# pcb_benelli.net
KiCad netlist of a schematic drawn in Altium Designer
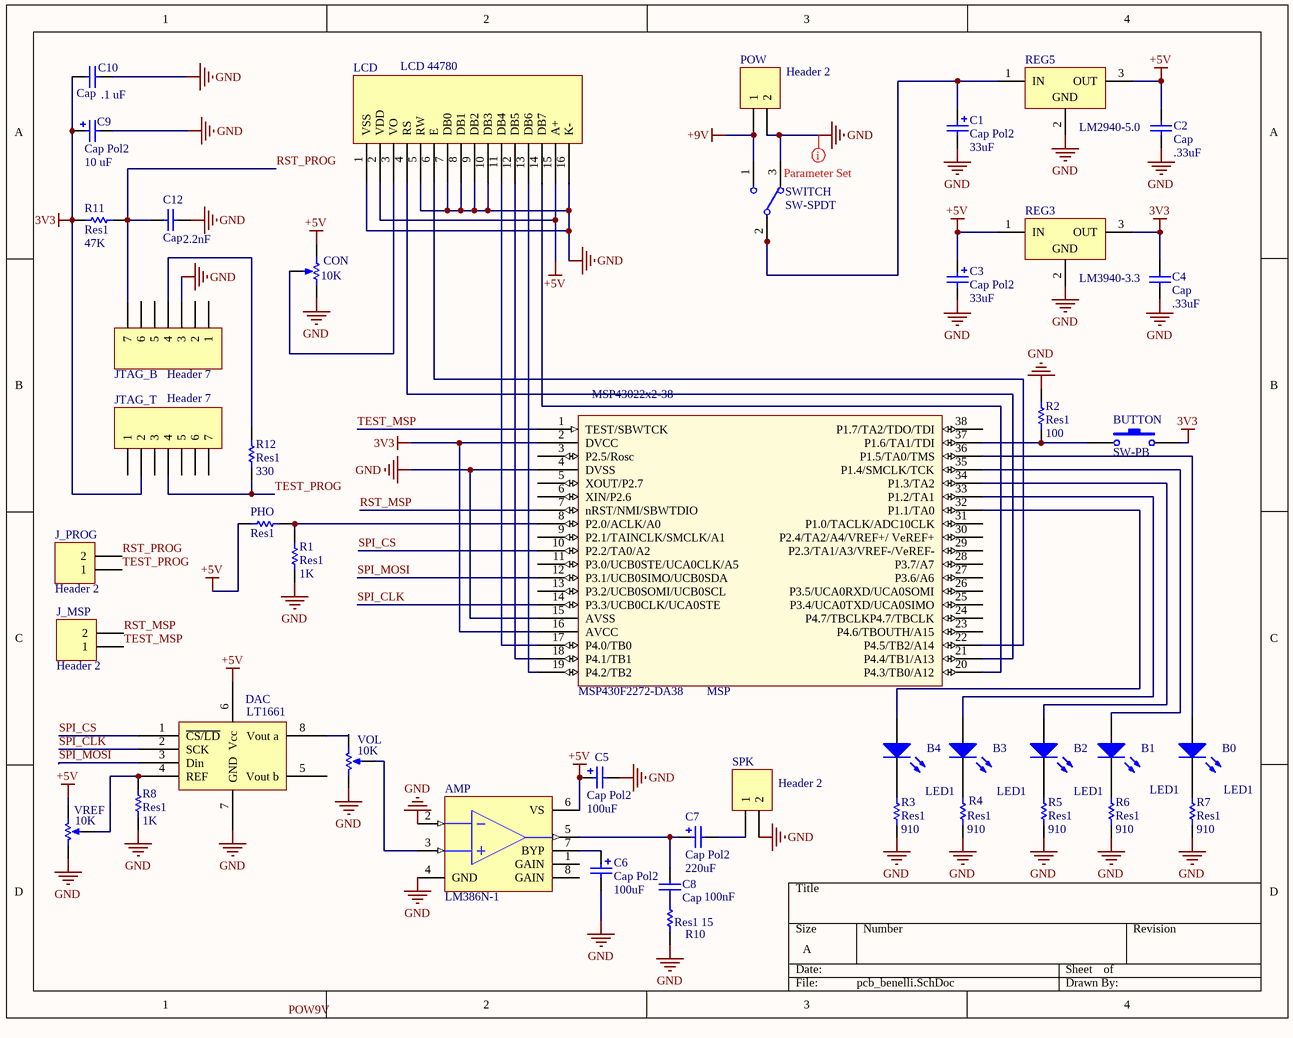
[diagram p0: pcb_benelli.SchDoc]

(export (version "E")
  (design (tool "Eeschema 10.0.6"))
  (components
    (comp (ref "AMP")
      (value "LM386N-1")
      (footprint "DIP-8")
      (description "Low-Voltage Audio Power Amplifier")
      (fields (field (name "PUBLISHER") "Altium Limited"))
      (libsource (lib "ECE LIB new") (part "LM386N-1"))
    )
    (comp (ref "B0")
      (value "LED1")
      (footprint "DIODE-0.4")
      (description "Typical RED GaAs LED")
      (fields (field (name "PUBLISHER") "Altium Limited"))
      (libsource (lib "Miscellaneous Devices") (part "LED1"))
    )
    (comp (ref "B1")
      (value "LED1")
      (footprint "DIODE-0.4")
      (description "Typical RED GaAs LED")
      (fields (field (name "PUBLISHER") "Altium Limited"))
      (libsource (lib "Miscellaneous Devices") (part "LED1"))
    )
    (comp (ref "B2")
      (value "LED1")
      (footprint "DIODE-0.4")
      (description "Typical RED GaAs LED")
      (fields (field (name "PUBLISHER") "Altium Limited"))
      (libsource (lib "Miscellaneous Devices") (part "LED1"))
    )
    (comp (ref "B3")
      (value "LED1")
      (footprint "DIODE-0.4")
      (description "Typical RED GaAs LED")
      (fields (field (name "PUBLISHER") "Altium Limited"))
      (libsource (lib "Miscellaneous Devices") (part "LED1"))
    )
    (comp (ref "B4")
      (value "LED1")
      (footprint "DIODE-0.4")
      (description "Typical RED GaAs LED")
      (fields (field (name "PUBLISHER") "Altium Limited"))
      (libsource (lib "Miscellaneous Devices") (part "LED1"))
    )
    (comp (ref "BUTTON")
      (value "SW-PB")
      (footprint "SW PB")
      (description "DIGIKEY SW400-ND")
      (fields (field (name "PUBLISHER") "Altium Limited"))
      (libsource (lib "ECE LIB new") (part "SW-PB"))
    )
    (comp (ref "C1")
      (value "Cap Pol2")
      (footprint "CAPR5-4X5")
      (description "Polarized Capacitor (Axial)")
      (fields (field (name "ALTIUM_VALUE") "33uF") (field (name "PUBLISHER") "Altium Limited"))
      (libsource (lib "Miscellaneous Devices") (part "Cap Pol2"))
    )
    (comp (ref "C2")
      (value "Cap")
      (footprint "RAD-0.3")
      (description "Capacitor")
      (fields (field (name "ALTIUM_VALUE") ".33uF") (field (name "PUBLISHER") "Altium Limited"))
      (libsource (lib "Miscellaneous Devices") (part "Cap"))
    )
    (comp (ref "C3")
      (value "Cap Pol2")
      (footprint "CAPR5-4X5")
      (description "Polarized Capacitor (Axial)")
      (fields (field (name "ALTIUM_VALUE") "33uF") (field (name "PUBLISHER") "Altium Limited"))
      (libsource (lib "Miscellaneous Devices") (part "Cap Pol2"))
    )
    (comp (ref "C4")
      (value "Cap")
      (footprint "RAD-0.3")
      (description "Capacitor")
      (fields (field (name "ALTIUM_VALUE") ".33uF") (field (name "PUBLISHER") "Altium Limited"))
      (libsource (lib "Miscellaneous Devices") (part "Cap"))
    )
    (comp (ref "C5")
      (value "Cap Pol2")
      (footprint "CAPR5-4X5")
      (description "Polarized Capacitor (Axial)")
      (fields (field (name "ALTIUM_VALUE") "100uF") (field (name "PUBLISHER") "Altium Limited"))
      (libsource (lib "Miscellaneous Devices") (part "Cap Pol2"))
    )
    (comp (ref "C6")
      (value "Cap Pol2")
      (footprint "CAPR5-4X5")
      (description "Polarized Capacitor (Axial)")
      (fields (field (name "ALTIUM_VALUE") "100uF") (field (name "PUBLISHER") "Altium Limited"))
      (libsource (lib "Miscellaneous Devices") (part "Cap Pol2"))
    )
    (comp (ref "C7")
      (value "Cap Pol2")
      (footprint "CAPR5-4X5")
      (description "Polarized Capacitor (Axial)")
      (fields (field (name "ALTIUM_VALUE") "220uF") (field (name "PUBLISHER") "Altium Limited"))
      (libsource (lib "Miscellaneous Devices") (part "Cap Pol2"))
    )
    (comp (ref "C8")
      (value "Cap")
      (footprint "RAD-0.3")
      (description "Capacitor")
      (fields (field (name "ALTIUM_VALUE") "100nF") (field (name "PUBLISHER") "Altium Limited"))
      (libsource (lib "Miscellaneous Devices") (part "Cap"))
    )
    (comp (ref "C9")
      (value "Cap Pol2")
      (footprint "CAPR5-4X5")
      (description "Polarized Capacitor (Axial)")
      (fields (field (name "ALTIUM_VALUE") "10 uF") (field (name "PUBLISHER") "Altium Limited"))
      (libsource (lib "Miscellaneous Devices") (part "Cap Pol2"))
    )
    (comp (ref "C10")
      (value "Cap")
      (footprint "RAD-0.3")
      (description "Capacitor")
      (fields (field (name "ALTIUM_VALUE") ".1 uF") (field (name "PUBLISHER") "Altium Limited"))
      (libsource (lib "Miscellaneous Devices") (part "Cap"))
    )
    (comp (ref "C12")
      (value "Cap")
      (footprint "RAD-0.3")
      (description "Capacitor")
      (fields (field (name "ALTIUM_VALUE") "2.2nF") (field (name "PUBLISHER") "Altium Limited"))
      (libsource (lib "Miscellaneous Devices") (part "Cap"))
    )
    (comp (ref "CON")
      (value "10K")
      (footprint "VR5")
      (description "Potentiometer")
      (fields (field (name "Comment") "RPot_3") (field (name "PUBLISHER") "Altium Limited"))
      (libsource (lib "ECE LIB new") (part "RPot"))
    )
    (comp (ref "DAC") (value "LT1661") (footprint "DIP-8") (libsource (lib "ECE LIB new") (part "LT1661")))
    (comp (ref "JTAG_B")
      (value "Header 7")
      (footprint "HDR1X7")
      (description "Header, 7-Pin")
      (fields (field (name "PUBLISHER") "Altium Limited"))
      (libsource (lib "") (part "Header 7_1"))
    )
    (comp (ref "JTAG_T")
      (value "Header 7")
      (footprint "HDR1X7")
      (description "Header, 7-Pin")
      (fields (field (name "PUBLISHER") "Altium Limited"))
      (libsource (lib "Miscellaneous Connectors") (part "Header 7"))
    )
    (comp (ref "J_MSP")
      (value "Header 2")
      (footprint "HDR1X2")
      (description "Header, 2-Pin")
      (fields (field (name "PUBLISHER") "Altium Limited"))
      (libsource (lib "") (part "Header 2_1"))
    )
    (comp (ref "J_PROG")
      (value "Header 2")
      (footprint "HDR1X2")
      (description "Header, 2-Pin")
      (fields (field (name "PUBLISHER") "Altium Limited"))
      (libsource (lib "") (part "Header 2_1"))
    )
    (comp (ref "LCD")
      (value "LCD 44780")
      (footprint "OLED 16x2")
      (libsource (lib "ECE LIB new") (part "LCD 44780"))
    )
    (comp (ref "MSP")
      (value "MSP430F2272-DA38")
      (footprint "DIP38")
      (libsource (lib "ECE LIB new") (part "MSP430F22x2-DA38"))
    )
    (comp (ref "PHO")
      (value "Res1")
      (footprint "AXIAL-0.3")
      (description "Resistor")
      (fields (field (name "PUBLISHER") "Altium Limited"))
      (libsource (lib "Miscellaneous Devices") (part "Res1"))
    )
    (comp (ref "POW")
      (value "Header 2")
      (footprint "HDR1X2")
      (description "Header, 2-Pin")
      (fields (field (name "PUBLISHER") "Altium Limited"))
      (libsource (lib "Miscellaneous Connectors") (part "Header 2"))
    )
    (comp (ref "R1")
      (value "Res1")
      (footprint "AXIAL-0.3")
      (description "Resistor")
      (fields (field (name "ALTIUM_VALUE") "1K") (field (name "PUBLISHER") "Altium Limited"))
      (libsource (lib "Miscellaneous Devices") (part "Res1"))
    )
    (comp (ref "R2")
      (value "Res1")
      (footprint "AXIAL-0.3")
      (description "Resistor")
      (fields (field (name "ALTIUM_VALUE") "100") (field (name "PUBLISHER") "Altium Limited"))
      (libsource (lib "Miscellaneous Devices") (part "Res1"))
    )
    (comp (ref "R3")
      (value "Res1")
      (footprint "AXIAL-0.3")
      (description "Resistor")
      (fields (field (name "ALTIUM_VALUE") "910") (field (name "PUBLISHER") "Altium Limited"))
      (libsource (lib "Miscellaneous Devices") (part "Res1"))
    )
    (comp (ref "R4")
      (value "Res1")
      (footprint "AXIAL-0.3")
      (description "Resistor")
      (fields (field (name "ALTIUM_VALUE") "910") (field (name "PUBLISHER") "Altium Limited"))
      (libsource (lib "Miscellaneous Devices") (part "Res1"))
    )
    (comp (ref "R5")
      (value "Res1")
      (footprint "AXIAL-0.3")
      (description "Resistor")
      (fields (field (name "ALTIUM_VALUE") "910") (field (name "PUBLISHER") "Altium Limited"))
      (libsource (lib "Miscellaneous Devices") (part "Res1"))
    )
    (comp (ref "R6")
      (value "Res1")
      (footprint "AXIAL-0.3")
      (description "Resistor")
      (fields (field (name "ALTIUM_VALUE") "910") (field (name "PUBLISHER") "Altium Limited"))
      (libsource (lib "Miscellaneous Devices") (part "Res1"))
    )
    (comp (ref "R7")
      (value "Res1")
      (footprint "AXIAL-0.3")
      (description "Resistor")
      (fields (field (name "ALTIUM_VALUE") "910") (field (name "PUBLISHER") "Altium Limited"))
      (libsource (lib "Miscellaneous Devices") (part "Res1"))
    )
    (comp (ref "R8")
      (value "Res1")
      (footprint "AXIAL-0.3")
      (description "Resistor")
      (fields (field (name "ALTIUM_VALUE") "1K") (field (name "PUBLISHER") "Altium Limited"))
      (libsource (lib "Miscellaneous Devices") (part "Res1"))
    )
    (comp (ref "R10")
      (value "Res1")
      (footprint "AXIAL-0.3")
      (description "Resistor")
      (fields (field (name "ALTIUM_VALUE") "15") (field (name "PUBLISHER") "Altium Limited"))
      (libsource (lib "Miscellaneous Devices") (part "Res1"))
    )
    (comp (ref "R11")
      (value "Res1")
      (footprint "AXIAL-0.3")
      (description "Resistor")
      (fields (field (name "ALTIUM_VALUE") "47K") (field (name "PUBLISHER") "Altium Limited"))
      (libsource (lib "Miscellaneous Devices") (part "Res1"))
    )
    (comp (ref "R12")
      (value "Res1")
      (footprint "AXIAL-0.3")
      (description "Resistor")
      (fields (field (name "ALTIUM_VALUE") "330") (field (name "PUBLISHER") "Altium Limited"))
      (libsource (lib "Miscellaneous Devices") (part "Res1"))
    )
    (comp (ref "REG3")
      (value "LM3940-3.3")
      (footprint "T03B")
      (description "1A Low Dropout Regulator, 3-pin TO-220")
      (fields
        (field (name "PARTNUMBER") "LM2940CT-3.3")
        (field (name "MANUFACTURER") "National Semiconductor")
      )
      (libsource (lib "ECE LIB new") (part "LM2940CT-5.0"))
    )
    (comp (ref "REG5")
      (value "LM2940-5.0")
      (footprint "T03B")
      (description "1A Low Dropout Regulator, 3-pin TO-220")
      (fields
        (field (name "PARTNUMBER") "LM2940CT-3.3")
        (field (name "MANUFACTURER") "National Semiconductor")
      )
      (libsource (lib "ECE LIB new") (part "LM2940CT-5.0"))
    )
    (comp (ref "SPK")
      (value "Header 2")
      (footprint "HDR1X2")
      (description "Header, 2-Pin")
      (fields (field (name "PUBLISHER") "Altium Limited"))
      (libsource (lib "Miscellaneous Connectors") (part "Header 2"))
    )
    (comp (ref "SWITCH")
      (value "SW-SPDT")
      (footprint "SW DPST jameco")
      (description "SPDT Subminiature Toggle Switch, Right Angle Mounting, Vertical Actuation")
      (fields (field (name "PUBLISHER") "Altium Limited"))
      (libsource (lib "ECE LIB new") (part "SW-SPDT"))
    )
    (comp (ref "VOL")
      (value "10K")
      (footprint "VR5")
      (description "Potentiometer")
      (fields (field (name "Comment") "RPot_3") (field (name "PUBLISHER") "Altium Limited"))
      (libsource (lib "ECE LIB new") (part "RPot"))
    )
    (comp (ref "VREF")
      (value "10K")
      (footprint "VR5")
      (description "Potentiometer")
      (fields (field (name "Comment") "RPot_3") (field (name "PUBLISHER") "Altium Limited"))
      (libsource (lib "ECE LIB new") (part "RPot"))
    )
  )
  (nets
    (net (code "1") (name "+5V") (class "Default")
      (node (ref "AMP") (pin "6") (pinfunction "VS_6") (pintype "power_in"))
      (node (ref "C2") (pin "2") (pinfunction "2_2") (pintype "passive"))
      (node (ref "C3") (pin "1") (pinfunction "1_1") (pintype "passive"))
      (node (ref "C5") (pin "1") (pinfunction "1_1") (pintype "passive"))
      (node (ref "CON") (pin "1") (pinfunction "TOP_1") (pintype "passive"))
      (node (ref "DAC") (pin "6") (pinfunction "Vcc_6") (pintype "passive"))
      (node (ref "LCD") (pin "15") (pinfunction "A+_15") (pintype "passive"))
      (node (ref "LCD") (pin "2") (pinfunction "VDD_2") (pintype "passive"))
      (node (ref "PHO") (pin "1") (pinfunction "1_1") (pintype "passive"))
      (node (ref "REG3") (pin "1") (pinfunction "IN_1") (pintype "power_in"))
      (node (ref "REG5") (pin "3") (pinfunction "OUT_3") (pintype "power_in"))
      (node (ref "VREF") (pin "1") (pinfunction "TOP_1") (pintype "passive"))
    )
    (net (code "2") (name "+9V") (class "Default")
      (node (ref "POW") (pin "1") (pinfunction "1_1") (pintype "passive"))
      (node (ref "SWITCH") (pin "1") (pinfunction "1_1") (pintype "passive"))
    )
    (net (code "4") (name "/RST_MSP") (class "Default")
      (node (ref "J_MSP") (pin "2") (pinfunction "2_2") (pintype "passive"))
      (node (ref "MSP") (pin "7") (pinfunction "nRST/NMI/SBWTDIO_7") (pintype "bidirectional"))
    )
    (net (code "5") (name "/RST_PROG") (class "Default")
      (node (ref "C12") (pin "1") (pinfunction "1_1") (pintype "passive"))
      (node (ref "JTAG_B") (pin "7") (pinfunction "7_7") (pintype "passive"))
      (node (ref "J_PROG") (pin "2") (pinfunction "2_2") (pintype "passive"))
      (node (ref "R11") (pin "2") (pinfunction "2_2") (pintype "passive"))
    )
    (net (code "6") (name "/SPI_CLK") (class "Default")
      (node (ref "DAC") (pin "2") (pinfunction "SCK_2") (pintype "passive"))
      (node (ref "MSP") (pin "14") (pinfunction "P3.3/UCB0CLK/UCA0STE_14") (pintype "bidirectional"))
    )
    (net (code "7") (name "/SPI_CS") (class "Default")
      (node (ref "DAC") (pin "1") (pinfunction "~{CS/LD}_1") (pintype "passive"))
      (node (ref "MSP") (pin "10") (pinfunction "P2.2/TA0/A2_10") (pintype "bidirectional"))
    )
    (net (code "8") (name "/SPI_MOSI") (class "Default")
      (node (ref "DAC") (pin "3") (pinfunction "Din_3") (pintype "passive"))
      (node (ref "MSP") (pin "12") (pinfunction "P3.1/UCB0SIMO/UCB0SDA_12") (pintype "bidirectional"))
    )
    (net (code "9") (name "/TEST_MSP") (class "Default")
      (node (ref "J_MSP") (pin "1") (pinfunction "1_1") (pintype "passive"))
      (node (ref "MSP") (pin "1") (pinfunction "TEST/SBWTCK_1") (pintype "input"))
    )
    (net (code "10") (name "/TEST_PROG") (class "Default")
      (node (ref "JTAG_T") (pin "4") (pinfunction "4_4") (pintype "passive"))
      (node (ref "J_PROG") (pin "1") (pinfunction "1_1") (pintype "passive"))
      (node (ref "R12") (pin "1") (pinfunction "1_1") (pintype "passive"))
    )
    (net (code "11") (name "3V3") (class "Default")
      (node (ref "BUTTON") (pin "2") (pinfunction "2_2") (pintype "passive"))
      (node (ref "C10") (pin "1") (pinfunction "1_1") (pintype "passive"))
      (node (ref "C4") (pin "2") (pinfunction "2_2") (pintype "passive"))
      (node (ref "C9") (pin "1") (pinfunction "1_1") (pintype "passive"))
      (node (ref "JTAG_T") (pin "2") (pinfunction "2_2") (pintype "passive"))
      (node (ref "MSP") (pin "16") (pinfunction "AVCC_16") (pintype "power_in"))
      (node (ref "MSP") (pin "2") (pinfunction "DVCC_2") (pintype "power_in"))
      (node (ref "R11") (pin "1") (pinfunction "1_1") (pintype "passive"))
      (node (ref "REG3") (pin "3") (pinfunction "OUT_3") (pintype "power_in"))
    )
    (net (code "12") (name "GND") (class "Default")
      (node (ref "AMP") (pin "2") (pinfunction "IN-_2") (pintype "input"))
      (node (ref "AMP") (pin "4") (pinfunction "GND_4") (pintype "power_in"))
      (node (ref "C1") (pin "2") (pinfunction "2_2") (pintype "passive"))
      (node (ref "C10") (pin "2") (pinfunction "2_2") (pintype "passive"))
      (node (ref "C12") (pin "2") (pinfunction "2_2") (pintype "passive"))
      (node (ref "C2") (pin "1") (pinfunction "1_1") (pintype "passive"))
      (node (ref "C3") (pin "2") (pinfunction "2_2") (pintype "passive"))
      (node (ref "C4") (pin "1") (pinfunction "1_1") (pintype "passive"))
      (node (ref "C5") (pin "2") (pinfunction "2_2") (pintype "passive"))
      (node (ref "C6") (pin "2") (pinfunction "2_2") (pintype "passive"))
      (node (ref "C9") (pin "2") (pinfunction "2_2") (pintype "passive"))
      (node (ref "CON") (pin "3") (pinfunction "BOT_3") (pintype "passive"))
      (node (ref "DAC") (pin "7") (pinfunction "GND_7") (pintype "passive"))
      (node (ref "JTAG_B") (pin "3") (pinfunction "3_3") (pintype "passive"))
      (node (ref "LCD") (pin "1") (pinfunction "VSS_1") (pintype "passive"))
      (node (ref "LCD") (pin "10") (pinfunction "DB3_10") (pintype "passive"))
      (node (ref "LCD") (pin "16") (pinfunction "K-_16") (pintype "passive"))
      (node (ref "LCD") (pin "5") (pinfunction "RW_5") (pintype "passive"))
      (node (ref "LCD") (pin "7") (pinfunction "DB0_7") (pintype "passive"))
      (node (ref "LCD") (pin "8") (pinfunction "DB1_8") (pintype "passive"))
      (node (ref "LCD") (pin "9") (pinfunction "DB2_9") (pintype "passive"))
      (node (ref "MSP") (pin "15") (pinfunction "AVSS_15") (pintype "power_in"))
      (node (ref "MSP") (pin "4") (pinfunction "DVSS_4") (pintype "power_in"))
      (node (ref "POW") (pin "2") (pinfunction "2_2") (pintype "passive"))
      (node (ref "R1") (pin "1") (pinfunction "1_1") (pintype "passive"))
      (node (ref "R10") (pin "1") (pinfunction "1_1") (pintype "passive"))
      (node (ref "R2") (pin "2") (pinfunction "2_2") (pintype "passive"))
      (node (ref "R3") (pin "2") (pinfunction "2_2") (pintype "passive"))
      (node (ref "R4") (pin "2") (pinfunction "2_2") (pintype "passive"))
      (node (ref "R5") (pin "2") (pinfunction "2_2") (pintype "passive"))
      (node (ref "R6") (pin "2") (pinfunction "2_2") (pintype "passive"))
      (node (ref "R7") (pin "2") (pinfunction "2_2") (pintype "passive"))
      (node (ref "R8") (pin "1") (pinfunction "1_1") (pintype "passive"))
      (node (ref "REG3") (pin "2") (pinfunction "GND_2") (pintype "power_in"))
      (node (ref "REG5") (pin "2") (pinfunction "GND_2") (pintype "power_in"))
      (node (ref "SPK") (pin "2") (pinfunction "2_2") (pintype "passive"))
      (node (ref "SWITCH") (pin "3") (pinfunction "3_3") (pintype "passive"))
      (node (ref "VOL") (pin "3") (pinfunction "BOT_3") (pintype "passive"))
      (node (ref "VREF") (pin "3") (pinfunction "BOT_3") (pintype "passive"))
    )
    (net (code "13") (name "Net-(AMP-BYP)") (class "Default")
      (node (ref "AMP") (pin "7") (pinfunction "BYP_7") (pintype "passive"))
      (node (ref "C6") (pin "1") (pinfunction "1_1") (pintype "passive"))
    )
    (net (code "14") (name "Net-(AMP-IN+)") (class "Default")
      (node (ref "AMP") (pin "3") (pinfunction "IN+_3") (pintype "input"))
      (node (ref "VOL") (pin "2") (pinfunction "TAP_2") (pintype "passive"))
    )
    (net (code "15") (name "Net-(AMP-OUT)") (class "Default")
      (node (ref "AMP") (pin "5") (pinfunction "OUT_5") (pintype "output"))
      (node (ref "C7") (pin "1") (pinfunction "1_1") (pintype "passive"))
      (node (ref "C8") (pin "2") (pinfunction "2_2") (pintype "passive"))
    )
    (net (code "16") (name "Net-(B0-A)") (class "Default")
      (node (ref "B0") (pin "1") (pinfunction "A_1") (pintype "passive"))
      (node (ref "MSP") (pin "36") (pinfunction "P1.5/TA0/TMS_36") (pintype "bidirectional"))
    )
    (net (code "17") (name "Net-(B0-K)") (class "Default")
      (node (ref "B0") (pin "2") (pinfunction "K_2") (pintype "passive"))
      (node (ref "R7") (pin "1") (pinfunction "1_1") (pintype "passive"))
    )
    (net (code "18") (name "Net-(B1-A)") (class "Default")
      (node (ref "B1") (pin "1") (pinfunction "A_1") (pintype "passive"))
      (node (ref "MSP") (pin "35") (pinfunction "P1.4/SMCLK/TCK_35") (pintype "bidirectional"))
    )
    (net (code "19") (name "Net-(B1-K)") (class "Default")
      (node (ref "B1") (pin "2") (pinfunction "K_2") (pintype "passive"))
      (node (ref "R6") (pin "1") (pinfunction "1_1") (pintype "passive"))
    )
    (net (code "20") (name "Net-(B2-A)") (class "Default")
      (node (ref "B2") (pin "1") (pinfunction "A_1") (pintype "passive"))
      (node (ref "MSP") (pin "34") (pinfunction "P1.3/TA2_34") (pintype "bidirectional"))
    )
    (net (code "21") (name "Net-(B2-K)") (class "Default")
      (node (ref "B2") (pin "2") (pinfunction "K_2") (pintype "passive"))
      (node (ref "R5") (pin "1") (pinfunction "1_1") (pintype "passive"))
    )
    (net (code "22") (name "Net-(B3-A)") (class "Default")
      (node (ref "B3") (pin "1") (pinfunction "A_1") (pintype "passive"))
      (node (ref "MSP") (pin "33") (pinfunction "P1.2/TA1_33") (pintype "bidirectional"))
    )
    (net (code "23") (name "Net-(B3-K)") (class "Default")
      (node (ref "B3") (pin "2") (pinfunction "K_2") (pintype "passive"))
      (node (ref "R4") (pin "1") (pinfunction "1_1") (pintype "passive"))
    )
    (net (code "24") (name "Net-(B4-A)") (class "Default")
      (node (ref "B4") (pin "1") (pinfunction "A_1") (pintype "passive"))
      (node (ref "MSP") (pin "32") (pinfunction "P1.1/TA0_32") (pintype "bidirectional"))
    )
    (net (code "25") (name "Net-(B4-K)") (class "Default")
      (node (ref "B4") (pin "2") (pinfunction "K_2") (pintype "passive"))
      (node (ref "R3") (pin "1") (pinfunction "1_1") (pintype "passive"))
    )
    (net (code "26") (name "Net-(C7-Pad2)") (class "Default")
      (node (ref "C7") (pin "2") (pinfunction "2_2") (pintype "passive"))
      (node (ref "SPK") (pin "1") (pinfunction "1_1") (pintype "passive"))
    )
    (net (code "27") (name "Net-(C8-Pad1)") (class "Default")
      (node (ref "C8") (pin "1") (pinfunction "1_1") (pintype "passive"))
      (node (ref "R10") (pin "2") (pinfunction "2_2") (pintype "passive"))
    )
    (net (code "28") (name "Net-(CON-TAP)") (class "Default")
      (node (ref "CON") (pin "2") (pinfunction "TAP_2") (pintype "passive"))
      (node (ref "LCD") (pin "3") (pinfunction "VO_3") (pintype "passive"))
    )
    (net (code "29") (name "Net-(DAC-REF)") (class "Default")
      (node (ref "DAC") (pin "4") (pinfunction "REF_4") (pintype "passive"))
      (node (ref "R8") (pin "2") (pinfunction "2_2") (pintype "passive"))
      (node (ref "VREF") (pin "2") (pinfunction "TAP_2") (pintype "passive"))
    )
    (net (code "30") (name "Net-(DAC-Vout_a)") (class "Default")
      (node (ref "DAC") (pin "8") (pinfunction "Vout_a_8") (pintype "passive"))
      (node (ref "VOL") (pin "1") (pinfunction "TOP_1") (pintype "passive"))
    )
    (net (code "31") (name "Net-(JTAG_B-Pad4)") (class "Default")
      (node (ref "JTAG_B") (pin "4") (pinfunction "4_4") (pintype "passive"))
      (node (ref "R12") (pin "2") (pinfunction "2_2") (pintype "passive"))
    )
    (net (code "32") (name "Net-(LCD-DB4)") (class "Default")
      (node (ref "LCD") (pin "11") (pinfunction "DB4_11") (pintype "passive"))
      (node (ref "MSP") (pin "17") (pinfunction "P4.0/TB0_17") (pintype "bidirectional"))
    )
    (net (code "33") (name "Net-(LCD-DB5)") (class "Default")
      (node (ref "LCD") (pin "12") (pinfunction "DB5_12") (pintype "passive"))
      (node (ref "MSP") (pin "18") (pinfunction "P4.1/TB1_18") (pintype "bidirectional"))
    )
    (net (code "34") (name "Net-(LCD-DB6)") (class "Default")
      (node (ref "LCD") (pin "13") (pinfunction "DB6_13") (pintype "passive"))
      (node (ref "MSP") (pin "19") (pinfunction "P4.2/TB2_19") (pintype "bidirectional"))
    )
    (net (code "35") (name "Net-(LCD-DB7)") (class "Default")
      (node (ref "LCD") (pin "14") (pinfunction "DB7_14") (pintype "passive"))
      (node (ref "MSP") (pin "20") (pinfunction "P4.3/TB0/A12_20") (pintype "bidirectional"))
    )
    (net (code "36") (name "Net-(LCD-E)") (class "Default")
      (node (ref "LCD") (pin "6") (pinfunction "E_6") (pintype "passive"))
      (node (ref "MSP") (pin "22") (pinfunction "P4.5/TB2/A14_22") (pintype "bidirectional"))
    )
    (net (code "37") (name "Net-(LCD-RS)") (class "Default")
      (node (ref "LCD") (pin "4") (pinfunction "RS_4") (pintype "passive"))
      (node (ref "MSP") (pin "21") (pinfunction "P4.4/TB1/A13_21") (pintype "bidirectional"))
    )
    (net (code "38") (name "Net-(MSP-P1.6{slash}TA1{slash}TDI)") (class "Default")
      (node (ref "BUTTON") (pin "1") (pinfunction "1_1") (pintype "passive"))
      (node (ref "MSP") (pin "37") (pinfunction "P1.6/TA1/TDI_37") (pintype "bidirectional"))
      (node (ref "R2") (pin "1") (pinfunction "1_1") (pintype "passive"))
    )
    (net (code "39") (name "Net-(MSP-P2.0{slash}ACLK{slash}A0)") (class "Default")
      (node (ref "MSP") (pin "8") (pinfunction "P2.0/ACLK/A0_8") (pintype "bidirectional"))
      (node (ref "PHO") (pin "2") (pinfunction "2_2") (pintype "passive"))
      (node (ref "R1") (pin "2") (pinfunction "2_2") (pintype "passive"))
    )
    (net (code "40") (name "Net-(REG5-IN)") (class "Default")
      (node (ref "C1") (pin "1") (pinfunction "1_1") (pintype "passive"))
      (node (ref "REG5") (pin "1") (pinfunction "IN_1") (pintype "power_in"))
      (node (ref "SWITCH") (pin "2") (pinfunction "2_2") (pintype "passive"))
    )
    (net (code "41") (name "unconnected-(AMP-GAIN-Pad1)") (class "Default")
      (node (ref "AMP") (pin "1") (pinfunction "GAIN_1") (pintype "passive"))
    )
    (net (code "42") (name "unconnected-(AMP-GAIN-Pad8)") (class "Default")
      (node (ref "AMP") (pin "8") (pinfunction "GAIN_8") (pintype "passive"))
    )
    (net (code "43") (name "unconnected-(DAC-Vout_b-Pad5)") (class "Default")
      (node (ref "DAC") (pin "5") (pinfunction "Vout_b_5") (pintype "passive"))
    )
    (net (code "44") (name "unconnected-(JTAG_B-Pad1)") (class "Default")
      (node (ref "JTAG_B") (pin "1") (pinfunction "1_1") (pintype "passive"))
    )
    (net (code "45") (name "unconnected-(JTAG_B-Pad2)") (class "Default")
      (node (ref "JTAG_B") (pin "2") (pinfunction "2_2") (pintype "passive"))
    )
    (net (code "46") (name "unconnected-(JTAG_B-Pad5)") (class "Default")
      (node (ref "JTAG_B") (pin "5") (pinfunction "5_5") (pintype "passive"))
    )
    (net (code "47") (name "unconnected-(JTAG_B-Pad6)") (class "Default")
      (node (ref "JTAG_B") (pin "6") (pinfunction "6_6") (pintype "passive"))
    )
    (net (code "48") (name "unconnected-(JTAG_T-Pad1)") (class "Default")
      (node (ref "JTAG_T") (pin "1") (pinfunction "1_1") (pintype "passive"))
    )
    (net (code "49") (name "unconnected-(JTAG_T-Pad3)") (class "Default")
      (node (ref "JTAG_T") (pin "3") (pinfunction "3_3") (pintype "passive"))
    )
    (net (code "50") (name "unconnected-(JTAG_T-Pad5)") (class "Default")
      (node (ref "JTAG_T") (pin "5") (pinfunction "5_5") (pintype "passive"))
    )
    (net (code "51") (name "unconnected-(JTAG_T-Pad6)") (class "Default")
      (node (ref "JTAG_T") (pin "6") (pinfunction "6_6") (pintype "passive"))
    )
    (net (code "52") (name "unconnected-(JTAG_T-Pad7)") (class "Default")
      (node (ref "JTAG_T") (pin "7") (pinfunction "7_7") (pintype "passive"))
    )
    (net (code "53") (name "unconnected-(MSP-P1.0{slash}TACLK{slash}ADC10CLK-Pad31)") (class "Default")
      (node (ref "MSP") (pin "31") (pinfunction "P1.0/TACLK/ADC10CLK_31") (pintype "bidirectional"))
    )
    (net (code "54") (name "unconnected-(MSP-P1.7{slash}TA2{slash}TDO{slash}TDI-Pad38)") (class "Default")
      (node (ref "MSP") (pin "38") (pinfunction "P1.7/TA2/TDO/TDI_38") (pintype "bidirectional"))
    )
    (net (code "55") (name "unconnected-(MSP-P2.1{slash}TAINCLK{slash}SMCLK{slash}A1-Pad9)") (class "Default")
      (node (ref "MSP") (pin "9") (pinfunction "P2.1/TAINCLK/SMCLK/A1_9") (pintype "bidirectional"))
    )
    (net (code "56") (name "unconnected-(MSP-P2.3{slash}TA1{slash}A3{slash}VREF-{slash}VeREF--Pad29)") (class "Default")
      (node (ref "MSP") (pin "29") (pinfunction "P2.3/TA1/A3/VREF-/VeREF-_29") (pintype "bidirectional"))
    )
    (net (code "57") (name "unconnected-(MSP-P2.4{slash}TA2{slash}A4{slash}VREF+{slash}_VeREF+-Pad30)") (class "Default")
      (node (ref "MSP") (pin "30") (pinfunction "P2.4/TA2/A4/VREF+/_VeREF+_30") (pintype "bidirectional"))
    )
    (net (code "58") (name "unconnected-(MSP-P2.5{slash}Rosc-Pad3)") (class "Default")
      (node (ref "MSP") (pin "3") (pinfunction "P2.5/Rosc_3") (pintype "bidirectional"))
    )
    (net (code "59") (name "unconnected-(MSP-P3.0{slash}UCB0STE{slash}UCA0CLK{slash}A5-Pad11)") (class "Default")
      (node (ref "MSP") (pin "11") (pinfunction "P3.0/UCB0STE/UCA0CLK/A5_11") (pintype "bidirectional"))
    )
    (net (code "60") (name "unconnected-(MSP-P3.2{slash}UCB0SOMI{slash}UCB0SCL-Pad13)") (class "Default")
      (node (ref "MSP") (pin "13") (pinfunction "P3.2/UCB0SOMI/UCB0SCL_13") (pintype "bidirectional"))
    )
    (net (code "61") (name "unconnected-(MSP-P3.4{slash}UCA0TXD{slash}UCA0SIMO-Pad25)") (class "Default")
      (node (ref "MSP") (pin "25") (pinfunction "P3.4/UCA0TXD/UCA0SIMO_25") (pintype "bidirectional"))
    )
    (net (code "62") (name "unconnected-(MSP-P3.5{slash}UCA0RXD{slash}UCA0SOMI-Pad26)") (class "Default")
      (node (ref "MSP") (pin "26") (pinfunction "P3.5/UCA0RXD/UCA0SOMI_26") (pintype "bidirectional"))
    )
    (net (code "63") (name "unconnected-(MSP-P3.6{slash}A6-Pad27)") (class "Default")
      (node (ref "MSP") (pin "27") (pinfunction "P3.6/A6_27") (pintype "bidirectional"))
    )
    (net (code "64") (name "unconnected-(MSP-P3.7{slash}A7-Pad28)") (class "Default")
      (node (ref "MSP") (pin "28") (pinfunction "P3.7/A7_28") (pintype "bidirectional"))
    )
    (net (code "65") (name "unconnected-(MSP-P4.6{slash}TBOUTH{slash}A15-Pad23)") (class "Default")
      (node (ref "MSP") (pin "23") (pinfunction "P4.6/TBOUTH/A15_23") (pintype "bidirectional"))
    )
    (net (code "66") (name "unconnected-(MSP-P4.7{slash}TBCLKP4.7{slash}TBCLK-Pad24)") (class "Default")
      (node (ref "MSP") (pin "24") (pinfunction "P4.7/TBCLKP4.7/TBCLK_24") (pintype "bidirectional"))
    )
    (net (code "67") (name "unconnected-(MSP-XIN{slash}P2.6-Pad6)") (class "Default")
      (node (ref "MSP") (pin "6") (pinfunction "XIN/P2.6_6") (pintype "bidirectional"))
    )
    (net (code "68") (name "unconnected-(MSP-XOUT{slash}P2.7-Pad5)") (class "Default")
      (node (ref "MSP") (pin "5") (pinfunction "XOUT/P2.7_5") (pintype "bidirectional"))
    )
  )
)
